# RFID_Brd_00.net
KiCad netlist of a schematic drawn in EAGLE
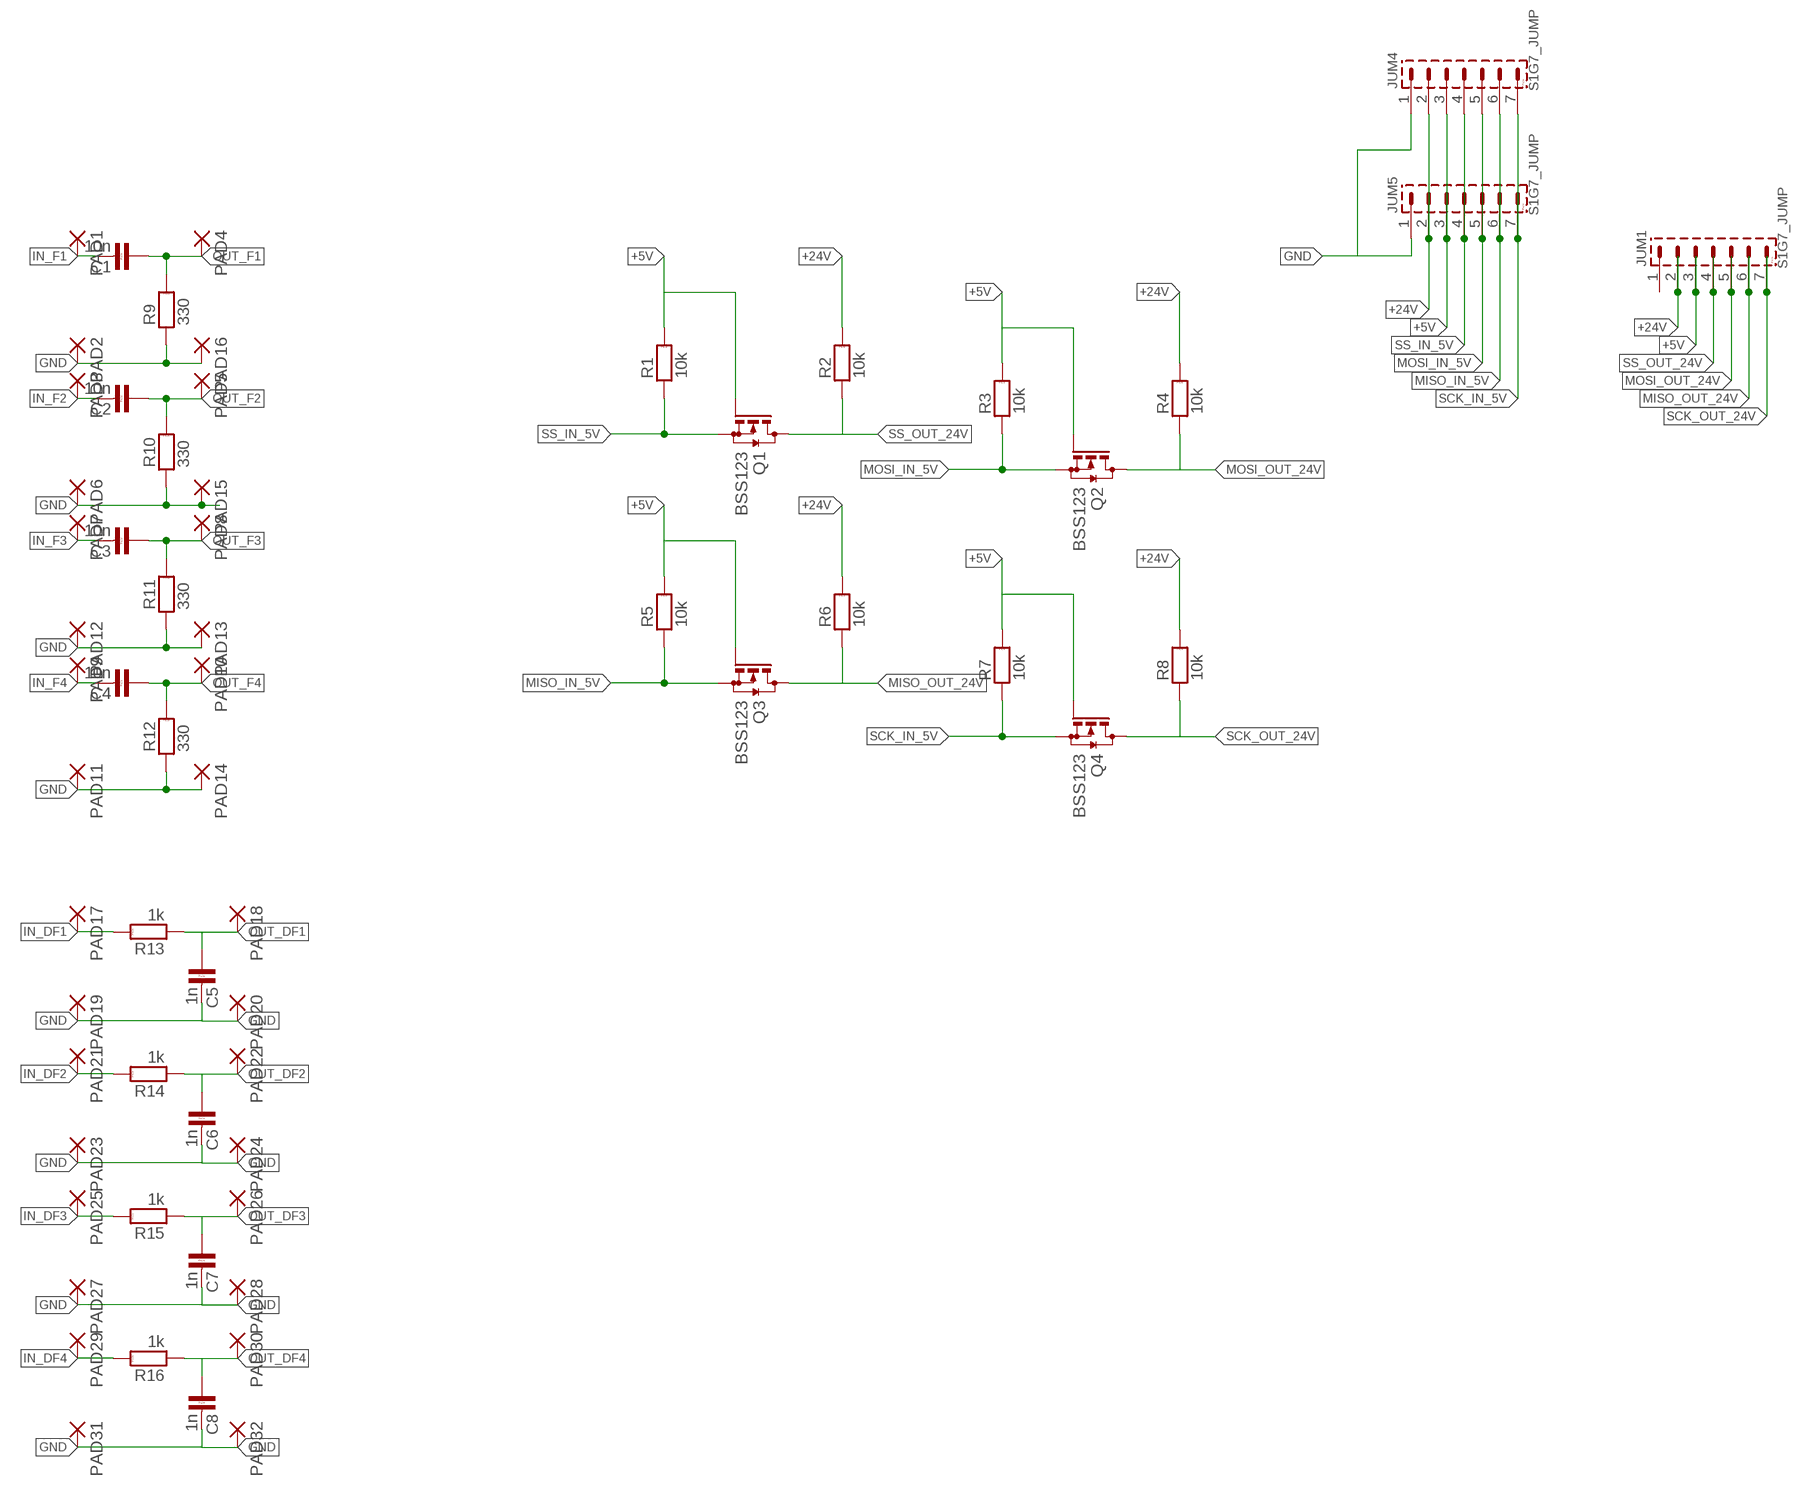
[diagram p0: schematic, sheet 1]

(export (version "E")
  (design (tool "Eeschema 10.0.6"))
  (components
    (comp (ref "C1")
      (value "10n")
      (footprint "eagle-import:1206")
      (libsource (lib "eagle-import") (part "C-KER_1206"))
    )
    (comp (ref "C2")
      (value "10n")
      (footprint "eagle-import:1206")
      (libsource (lib "eagle-import") (part "C-KER_1206"))
    )
    (comp (ref "C3")
      (value "10n")
      (footprint "eagle-import:1206")
      (libsource (lib "eagle-import") (part "C-KER_1206"))
    )
    (comp (ref "C4")
      (value "10n")
      (footprint "eagle-import:1206")
      (libsource (lib "eagle-import") (part "C-KER_1206"))
    )
    (comp (ref "C5")
      (value "1n")
      (footprint "eagle-import:1206")
      (libsource (lib "eagle-import") (part "C-KER_1206"))
    )
    (comp (ref "C6")
      (value "1n")
      (footprint "eagle-import:1206")
      (libsource (lib "eagle-import") (part "C-KER_1206"))
    )
    (comp (ref "C7")
      (value "1n")
      (footprint "eagle-import:1206")
      (libsource (lib "eagle-import") (part "C-KER_1206"))
    )
    (comp (ref "C8")
      (value "1n")
      (footprint "eagle-import:1206")
      (libsource (lib "eagle-import") (part "C-KER_1206"))
    )
    (comp (ref "JUM1")
      (value "S1G7_JUMP")
      (footprint "eagle-import:S1G7_JUM")
      (libsource (lib "eagle-import") (part "S1G7_JUMP"))
    )
    (comp (ref "JUM4")
      (value "S1G7_JUMP")
      (footprint "eagle-import:S1G7_JUM")
      (libsource (lib "eagle-import") (part "S1G7_JUMP"))
    )
    (comp (ref "JUM5")
      (value "S1G7_JUMP")
      (footprint "eagle-import:S1G7_JUM")
      (libsource (lib "eagle-import") (part "S1G7_JUMP"))
    )
    (comp (ref "PAD1")
      (value "SMD2")
      (footprint "eagle-import:SMD1,27-2,54")
      (libsource (lib "eagle-import") (part "SMD2"))
    )
    (comp (ref "PAD2")
      (value "SMD2")
      (footprint "eagle-import:SMD1,27-2,54")
      (libsource (lib "eagle-import") (part "SMD2"))
    )
    (comp (ref "PAD3")
      (value "SMD2")
      (footprint "eagle-import:SMD1,27-2,54")
      (libsource (lib "eagle-import") (part "SMD2"))
    )
    (comp (ref "PAD4")
      (value "SMD2")
      (footprint "eagle-import:SMD1,27-2,54")
      (libsource (lib "eagle-import") (part "SMD2"))
    )
    (comp (ref "PAD5")
      (value "SMD2")
      (footprint "eagle-import:SMD1,27-2,54")
      (libsource (lib "eagle-import") (part "SMD2"))
    )
    (comp (ref "PAD6")
      (value "SMD2")
      (footprint "eagle-import:SMD1,27-2,54")
      (libsource (lib "eagle-import") (part "SMD2"))
    )
    (comp (ref "PAD7")
      (value "SMD2")
      (footprint "eagle-import:SMD1,27-2,54")
      (libsource (lib "eagle-import") (part "SMD2"))
    )
    (comp (ref "PAD8")
      (value "SMD2")
      (footprint "eagle-import:SMD1,27-2,54")
      (libsource (lib "eagle-import") (part "SMD2"))
    )
    (comp (ref "PAD9")
      (value "SMD2")
      (footprint "eagle-import:SMD1,27-2,54")
      (libsource (lib "eagle-import") (part "SMD2"))
    )
    (comp (ref "PAD10")
      (value "SMD2")
      (footprint "eagle-import:SMD1,27-2,54")
      (libsource (lib "eagle-import") (part "SMD2"))
    )
    (comp (ref "PAD11")
      (value "SMD2")
      (footprint "eagle-import:SMD1,27-2,54")
      (libsource (lib "eagle-import") (part "SMD2"))
    )
    (comp (ref "PAD12")
      (value "SMD2")
      (footprint "eagle-import:SMD1,27-2,54")
      (libsource (lib "eagle-import") (part "SMD2"))
    )
    (comp (ref "PAD13")
      (value "SMD2")
      (footprint "eagle-import:SMD1,27-2,54")
      (libsource (lib "eagle-import") (part "SMD2"))
    )
    (comp (ref "PAD14")
      (value "SMD2")
      (footprint "eagle-import:SMD1,27-2,54")
      (libsource (lib "eagle-import") (part "SMD2"))
    )
    (comp (ref "PAD15")
      (value "SMD2")
      (footprint "eagle-import:SMD1,27-2,54")
      (libsource (lib "eagle-import") (part "SMD2"))
    )
    (comp (ref "PAD16")
      (value "SMD2")
      (footprint "eagle-import:SMD1,27-2,54")
      (libsource (lib "eagle-import") (part "SMD2"))
    )
    (comp (ref "PAD17")
      (value "SMD2")
      (footprint "eagle-import:SMD1,27-2,54")
      (libsource (lib "eagle-import") (part "SMD2"))
    )
    (comp (ref "PAD18")
      (value "SMD2")
      (footprint "eagle-import:SMD1,27-2,54")
      (libsource (lib "eagle-import") (part "SMD2"))
    )
    (comp (ref "PAD19")
      (value "SMD2")
      (footprint "eagle-import:SMD1,27-2,54")
      (libsource (lib "eagle-import") (part "SMD2"))
    )
    (comp (ref "PAD20")
      (value "SMD2")
      (footprint "eagle-import:SMD1,27-2,54")
      (libsource (lib "eagle-import") (part "SMD2"))
    )
    (comp (ref "PAD21")
      (value "SMD2")
      (footprint "eagle-import:SMD1,27-2,54")
      (libsource (lib "eagle-import") (part "SMD2"))
    )
    (comp (ref "PAD22")
      (value "SMD2")
      (footprint "eagle-import:SMD1,27-2,54")
      (libsource (lib "eagle-import") (part "SMD2"))
    )
    (comp (ref "PAD23")
      (value "SMD2")
      (footprint "eagle-import:SMD1,27-2,54")
      (libsource (lib "eagle-import") (part "SMD2"))
    )
    (comp (ref "PAD24")
      (value "SMD2")
      (footprint "eagle-import:SMD1,27-2,54")
      (libsource (lib "eagle-import") (part "SMD2"))
    )
    (comp (ref "PAD25")
      (value "SMD2")
      (footprint "eagle-import:SMD1,27-2,54")
      (libsource (lib "eagle-import") (part "SMD2"))
    )
    (comp (ref "PAD26")
      (value "SMD2")
      (footprint "eagle-import:SMD1,27-2,54")
      (libsource (lib "eagle-import") (part "SMD2"))
    )
    (comp (ref "PAD27")
      (value "SMD2")
      (footprint "eagle-import:SMD1,27-2,54")
      (libsource (lib "eagle-import") (part "SMD2"))
    )
    (comp (ref "PAD28")
      (value "SMD2")
      (footprint "eagle-import:SMD1,27-2,54")
      (libsource (lib "eagle-import") (part "SMD2"))
    )
    (comp (ref "PAD29")
      (value "SMD2")
      (footprint "eagle-import:SMD1,27-2,54")
      (libsource (lib "eagle-import") (part "SMD2"))
    )
    (comp (ref "PAD30")
      (value "SMD2")
      (footprint "eagle-import:SMD1,27-2,54")
      (libsource (lib "eagle-import") (part "SMD2"))
    )
    (comp (ref "PAD31")
      (value "SMD2")
      (footprint "eagle-import:SMD1,27-2,54")
      (libsource (lib "eagle-import") (part "SMD2"))
    )
    (comp (ref "PAD32")
      (value "SMD2")
      (footprint "eagle-import:SMD1,27-2,54")
      (libsource (lib "eagle-import") (part "SMD2"))
    )
    (comp (ref "Q1")
      (value "BSS123")
      (footprint "eagle-import:SOT23")
      (libsource (lib "eagle-import") (part "BSS123"))
    )
    (comp (ref "Q2")
      (value "BSS123")
      (footprint "eagle-import:SOT23")
      (libsource (lib "eagle-import") (part "BSS123"))
    )
    (comp (ref "Q3")
      (value "BSS123")
      (footprint "eagle-import:SOT23")
      (libsource (lib "eagle-import") (part "BSS123"))
    )
    (comp (ref "Q4")
      (value "BSS123")
      (footprint "eagle-import:SOT23")
      (libsource (lib "eagle-import") (part "BSS123"))
    )
    (comp (ref "R1")
      (value "10k")
      (footprint "eagle-import:1206")
      (libsource (lib "eagle-import") (part "R_1206"))
    )
    (comp (ref "R2")
      (value "10k")
      (footprint "eagle-import:1206")
      (libsource (lib "eagle-import") (part "R_1206"))
    )
    (comp (ref "R3")
      (value "10k")
      (footprint "eagle-import:1206")
      (libsource (lib "eagle-import") (part "R_1206"))
    )
    (comp (ref "R4")
      (value "10k")
      (footprint "eagle-import:1206")
      (libsource (lib "eagle-import") (part "R_1206"))
    )
    (comp (ref "R5")
      (value "10k")
      (footprint "eagle-import:1206")
      (libsource (lib "eagle-import") (part "R_1206"))
    )
    (comp (ref "R6")
      (value "10k")
      (footprint "eagle-import:1206")
      (libsource (lib "eagle-import") (part "R_1206"))
    )
    (comp (ref "R7")
      (value "10k")
      (footprint "eagle-import:1206")
      (libsource (lib "eagle-import") (part "R_1206"))
    )
    (comp (ref "R8")
      (value "10k")
      (footprint "eagle-import:1206")
      (libsource (lib "eagle-import") (part "R_1206"))
    )
    (comp (ref "R9")
      (value "330")
      (footprint "eagle-import:1206")
      (libsource (lib "eagle-import") (part "R_1206"))
    )
    (comp (ref "R10")
      (value "330")
      (footprint "eagle-import:1206")
      (libsource (lib "eagle-import") (part "R_1206"))
    )
    (comp (ref "R11")
      (value "330")
      (footprint "eagle-import:1206")
      (libsource (lib "eagle-import") (part "R_1206"))
    )
    (comp (ref "R12")
      (value "330")
      (footprint "eagle-import:1206")
      (libsource (lib "eagle-import") (part "R_1206"))
    )
    (comp (ref "R13")
      (value "1k")
      (footprint "eagle-import:1206")
      (libsource (lib "eagle-import") (part "R_1206"))
    )
    (comp (ref "R14")
      (value "1k")
      (footprint "eagle-import:1206")
      (libsource (lib "eagle-import") (part "R_1206"))
    )
    (comp (ref "R15")
      (value "1k")
      (footprint "eagle-import:1206")
      (libsource (lib "eagle-import") (part "R_1206"))
    )
    (comp (ref "R16")
      (value "1k")
      (footprint "eagle-import:1206")
      (libsource (lib "eagle-import") (part "R_1206"))
    )
  )
  (nets
    (net (code "1") (name "+5V") (class "Default")
      (node (ref "JUM1") (pin "3") (pinfunction "3_3") (pintype "passive"))
      (node (ref "JUM4") (pin "3") (pinfunction "3_3") (pintype "passive"))
      (node (ref "JUM5") (pin "3") (pinfunction "3_3") (pintype "passive"))
      (node (ref "Q1") (pin "1") (pinfunction "G_1") (pintype "passive"))
      (node (ref "Q2") (pin "1") (pinfunction "G_1") (pintype "passive"))
      (node (ref "Q3") (pin "1") (pinfunction "G_1") (pintype "passive"))
      (node (ref "Q4") (pin "1") (pinfunction "G_1") (pintype "passive"))
      (node (ref "R1") (pin "2") (pinfunction "2_2") (pintype "passive"))
      (node (ref "R3") (pin "2") (pinfunction "2_2") (pintype "passive"))
      (node (ref "R5") (pin "2") (pinfunction "2_2") (pintype "passive"))
      (node (ref "R7") (pin "2") (pinfunction "2_2") (pintype "passive"))
    )
    (net (code "2") (name "+24V") (class "Default")
      (node (ref "JUM1") (pin "2") (pinfunction "2_2") (pintype "passive"))
      (node (ref "JUM4") (pin "2") (pinfunction "2_2") (pintype "passive"))
      (node (ref "JUM5") (pin "2") (pinfunction "2_2") (pintype "passive"))
      (node (ref "R2") (pin "2") (pinfunction "2_2") (pintype "passive"))
      (node (ref "R4") (pin "2") (pinfunction "2_2") (pintype "passive"))
      (node (ref "R6") (pin "2") (pinfunction "2_2") (pintype "passive"))
      (node (ref "R8") (pin "2") (pinfunction "2_2") (pintype "passive"))
    )
    (net (code "3") (name "GND") (class "Default")
      (node (ref "C5") (pin "2") (pinfunction "2_2") (pintype "passive"))
      (node (ref "C6") (pin "2") (pinfunction "2_2") (pintype "passive"))
      (node (ref "C7") (pin "2") (pinfunction "2_2") (pintype "passive"))
      (node (ref "C8") (pin "2") (pinfunction "2_2") (pintype "passive"))
      (node (ref "JUM4") (pin "1") (pinfunction "1_1") (pintype "passive"))
      (node (ref "JUM5") (pin "1") (pinfunction "1_1") (pintype "passive"))
      (node (ref "PAD11") (pin "1") (pinfunction "P_1") (pintype "passive"))
      (node (ref "PAD12") (pin "1") (pinfunction "P_1") (pintype "passive"))
      (node (ref "PAD13") (pin "1") (pinfunction "P_1") (pintype "passive"))
      (node (ref "PAD14") (pin "1") (pinfunction "P_1") (pintype "passive"))
      (node (ref "PAD15") (pin "1") (pinfunction "P_1") (pintype "passive"))
      (node (ref "PAD16") (pin "1") (pinfunction "P_1") (pintype "passive"))
      (node (ref "PAD19") (pin "1") (pinfunction "P_1") (pintype "passive"))
      (node (ref "PAD2") (pin "1") (pinfunction "P_1") (pintype "passive"))
      (node (ref "PAD20") (pin "1") (pinfunction "P_1") (pintype "passive"))
      (node (ref "PAD23") (pin "1") (pinfunction "P_1") (pintype "passive"))
      (node (ref "PAD24") (pin "1") (pinfunction "P_1") (pintype "passive"))
      (node (ref "PAD27") (pin "1") (pinfunction "P_1") (pintype "passive"))
      (node (ref "PAD28") (pin "1") (pinfunction "P_1") (pintype "passive"))
      (node (ref "PAD31") (pin "1") (pinfunction "P_1") (pintype "passive"))
      (node (ref "PAD32") (pin "1") (pinfunction "P_1") (pintype "passive"))
      (node (ref "PAD6") (pin "1") (pinfunction "P_1") (pintype "passive"))
      (node (ref "R10") (pin "1") (pinfunction "1_1") (pintype "passive"))
      (node (ref "R11") (pin "1") (pinfunction "1_1") (pintype "passive"))
      (node (ref "R12") (pin "1") (pinfunction "1_1") (pintype "passive"))
      (node (ref "R9") (pin "1") (pinfunction "1_1") (pintype "passive"))
    )
    (net (code "4") (name "IN_DF1") (class "Default")
      (node (ref "PAD17") (pin "1") (pinfunction "P_1") (pintype "passive"))
      (node (ref "R13") (pin "2") (pinfunction "2_2") (pintype "passive"))
    )
    (net (code "5") (name "IN_DF2") (class "Default")
      (node (ref "PAD21") (pin "1") (pinfunction "P_1") (pintype "passive"))
      (node (ref "R14") (pin "2") (pinfunction "2_2") (pintype "passive"))
    )
    (net (code "6") (name "IN_DF3") (class "Default")
      (node (ref "PAD25") (pin "1") (pinfunction "P_1") (pintype "passive"))
      (node (ref "R15") (pin "2") (pinfunction "2_2") (pintype "passive"))
    )
    (net (code "7") (name "IN_DF4") (class "Default")
      (node (ref "PAD29") (pin "1") (pinfunction "P_1") (pintype "passive"))
      (node (ref "R16") (pin "2") (pinfunction "2_2") (pintype "passive"))
    )
    (net (code "8") (name "IN_F1") (class "Default")
      (node (ref "C1") (pin "2") (pinfunction "2_2") (pintype "passive"))
      (node (ref "PAD1") (pin "1") (pinfunction "P_1") (pintype "passive"))
    )
    (net (code "9") (name "IN_F2") (class "Default")
      (node (ref "C2") (pin "2") (pinfunction "2_2") (pintype "passive"))
      (node (ref "PAD3") (pin "1") (pinfunction "P_1") (pintype "passive"))
    )
    (net (code "10") (name "IN_F3") (class "Default")
      (node (ref "C3") (pin "2") (pinfunction "2_2") (pintype "passive"))
      (node (ref "PAD7") (pin "1") (pinfunction "P_1") (pintype "passive"))
    )
    (net (code "11") (name "IN_F4") (class "Default")
      (node (ref "C4") (pin "2") (pinfunction "2_2") (pintype "passive"))
      (node (ref "PAD9") (pin "1") (pinfunction "P_1") (pintype "passive"))
    )
    (net (code "12") (name "MISO_IN_5V") (class "Default")
      (node (ref "JUM4") (pin "6") (pinfunction "6_6") (pintype "passive"))
      (node (ref "JUM5") (pin "6") (pinfunction "6_6") (pintype "passive"))
      (node (ref "Q3") (pin "2") (pinfunction "S_2") (pintype "passive"))
      (node (ref "R5") (pin "1") (pinfunction "1_1") (pintype "passive"))
    )
    (net (code "13") (name "MISO_OUT_24V") (class "Default")
      (node (ref "JUM1") (pin "6") (pinfunction "6_6") (pintype "passive"))
      (node (ref "Q3") (pin "3") (pinfunction "D_3") (pintype "passive"))
      (node (ref "R6") (pin "1") (pinfunction "1_1") (pintype "passive"))
    )
    (net (code "14") (name "MOSI_IN_5V") (class "Default")
      (node (ref "JUM4") (pin "5") (pinfunction "5_5") (pintype "passive"))
      (node (ref "JUM5") (pin "5") (pinfunction "5_5") (pintype "passive"))
      (node (ref "Q2") (pin "2") (pinfunction "S_2") (pintype "passive"))
      (node (ref "R3") (pin "1") (pinfunction "1_1") (pintype "passive"))
    )
    (net (code "15") (name "MOSI_OUT_24V") (class "Default")
      (node (ref "JUM1") (pin "5") (pinfunction "5_5") (pintype "passive"))
      (node (ref "Q2") (pin "3") (pinfunction "D_3") (pintype "passive"))
      (node (ref "R4") (pin "1") (pinfunction "1_1") (pintype "passive"))
    )
    (net (code "16") (name "OUT_DF1") (class "Default")
      (node (ref "C5") (pin "1") (pinfunction "1_1") (pintype "passive"))
      (node (ref "PAD18") (pin "1") (pinfunction "P_1") (pintype "passive"))
      (node (ref "R13") (pin "1") (pinfunction "1_1") (pintype "passive"))
    )
    (net (code "17") (name "OUT_DF2") (class "Default")
      (node (ref "C6") (pin "1") (pinfunction "1_1") (pintype "passive"))
      (node (ref "PAD22") (pin "1") (pinfunction "P_1") (pintype "passive"))
      (node (ref "R14") (pin "1") (pinfunction "1_1") (pintype "passive"))
    )
    (net (code "18") (name "OUT_DF3") (class "Default")
      (node (ref "C7") (pin "1") (pinfunction "1_1") (pintype "passive"))
      (node (ref "PAD26") (pin "1") (pinfunction "P_1") (pintype "passive"))
      (node (ref "R15") (pin "1") (pinfunction "1_1") (pintype "passive"))
    )
    (net (code "19") (name "OUT_DF4") (class "Default")
      (node (ref "C8") (pin "1") (pinfunction "1_1") (pintype "passive"))
      (node (ref "PAD30") (pin "1") (pinfunction "P_1") (pintype "passive"))
      (node (ref "R16") (pin "1") (pinfunction "1_1") (pintype "passive"))
    )
    (net (code "20") (name "OUT_F1") (class "Default")
      (node (ref "C1") (pin "1") (pinfunction "1_1") (pintype "passive"))
      (node (ref "PAD4") (pin "1") (pinfunction "P_1") (pintype "passive"))
      (node (ref "R9") (pin "2") (pinfunction "2_2") (pintype "passive"))
    )
    (net (code "21") (name "OUT_F2") (class "Default")
      (node (ref "C2") (pin "1") (pinfunction "1_1") (pintype "passive"))
      (node (ref "PAD5") (pin "1") (pinfunction "P_1") (pintype "passive"))
      (node (ref "R10") (pin "2") (pinfunction "2_2") (pintype "passive"))
    )
    (net (code "22") (name "OUT_F3") (class "Default")
      (node (ref "C3") (pin "1") (pinfunction "1_1") (pintype "passive"))
      (node (ref "PAD8") (pin "1") (pinfunction "P_1") (pintype "passive"))
      (node (ref "R11") (pin "2") (pinfunction "2_2") (pintype "passive"))
    )
    (net (code "23") (name "OUT_F4") (class "Default")
      (node (ref "C4") (pin "1") (pinfunction "1_1") (pintype "passive"))
      (node (ref "PAD10") (pin "1") (pinfunction "P_1") (pintype "passive"))
      (node (ref "R12") (pin "2") (pinfunction "2_2") (pintype "passive"))
    )
    (net (code "24") (name "SCK_IN_5V") (class "Default")
      (node (ref "JUM4") (pin "7") (pinfunction "7_7") (pintype "passive"))
      (node (ref "JUM5") (pin "7") (pinfunction "7_7") (pintype "passive"))
      (node (ref "Q4") (pin "2") (pinfunction "S_2") (pintype "passive"))
      (node (ref "R7") (pin "1") (pinfunction "1_1") (pintype "passive"))
    )
    (net (code "25") (name "SCK_OUT_24V") (class "Default")
      (node (ref "JUM1") (pin "7") (pinfunction "7_7") (pintype "passive"))
      (node (ref "Q4") (pin "3") (pinfunction "D_3") (pintype "passive"))
      (node (ref "R8") (pin "1") (pinfunction "1_1") (pintype "passive"))
    )
    (net (code "26") (name "SS_IN_5V") (class "Default")
      (node (ref "JUM4") (pin "4") (pinfunction "4_4") (pintype "passive"))
      (node (ref "JUM5") (pin "4") (pinfunction "4_4") (pintype "passive"))
      (node (ref "Q1") (pin "2") (pinfunction "S_2") (pintype "passive"))
      (node (ref "R1") (pin "1") (pinfunction "1_1") (pintype "passive"))
    )
    (net (code "27") (name "SS_OUT_24V") (class "Default")
      (node (ref "JUM1") (pin "4") (pinfunction "4_4") (pintype "passive"))
      (node (ref "Q1") (pin "3") (pinfunction "D_3") (pintype "passive"))
      (node (ref "R2") (pin "1") (pinfunction "1_1") (pintype "passive"))
    )
    (net (code "28") (name "unconnected-(JUM1-Pad1)") (class "Default")
      (node (ref "JUM1") (pin "1") (pinfunction "1_1") (pintype "passive"))
    )
  )
)
